# INTELMOTICS.net
KiCad netlist of a schematic drawn in EAGLE
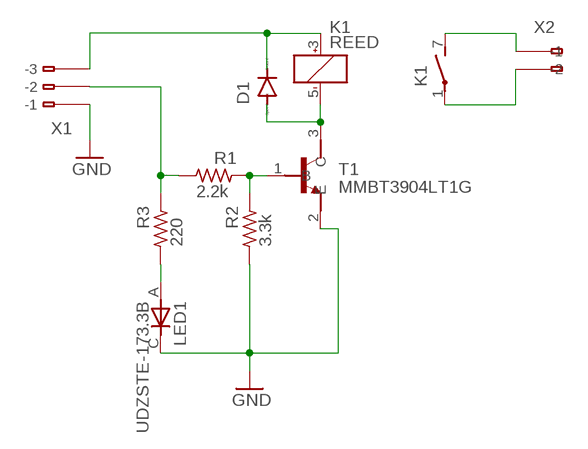
[diagram p0: schematic, sheet 1]

(export (version "E")
  (design (tool "Eeschema 10.0.6"))
  (components
    (comp (ref "D1")
      (value "MBR0520LT")
      (footprint "eagle-import:SOD123")
      (libsource (lib "eagle-import") (part "MBR0520LT"))
    )
    (comp (ref "K1")
      (value "REED")
      (footprint "eagle-import:REED")
      (libsource (lib "eagle-import") (part "REED"))
    )
    (comp (ref "LED1")
      (value "UDZSTE-173.3B")
      (footprint "eagle-import:SODFL2512X90N")
      (fields (field (name "MF") "Rohm"))
      (libsource (lib "eagle-import") (part "UDZSTE-173.3B"))
    )
    (comp (ref "R1")
      (value "2.2k")
      (footprint "eagle-import:R1206W")
      (libsource (lib "eagle-import") (part "R_1206W"))
    )
    (comp (ref "R2")
      (value "3.3k")
      (footprint "eagle-import:R1206W")
      (libsource (lib "eagle-import") (part "R_1206W"))
    )
    (comp (ref "R3")
      (value "220")
      (footprint "eagle-import:R1206W")
      (libsource (lib "eagle-import") (part "R_1206W"))
    )
    (comp (ref "T1")
      (value "MMBT3904LT1G")
      (footprint "eagle-import:SOT95P240X111-3N")
      (fields (field (name "MF") "ON Semiconductor"))
      (libsource (lib "eagle-import") (part "MMBT3904LT1G"))
    )
    (comp (ref "X1")
      (value "234-203")
      (footprint "eagle-import:234-203")
      (libsource (lib "eagle-import") (part "234-203"))
    )
    (comp (ref "X2")
      (value "234-502")
      (footprint "eagle-import:234-502")
      (libsource (lib "eagle-import") (part "234-502"))
    )
  )
  (nets
    (net (code "1") (name "GND") (class "Default")
      (node (ref "LED1") (pin "C") (pinfunction "C_C") (pintype "passive"))
      (node (ref "R2") (pin "1") (pinfunction "1_1") (pintype "passive"))
      (node (ref "T1") (pin "2") (pinfunction "E_2") (pintype "passive"))
      (node (ref "X1") (pin "B1") (pinfunction "B-1_B1") (pintype "passive"))
    )
    (net (code "2") (name "Net-(K1A-+)") (class "Default")
      (node (ref "D1") (pin "C") (pinfunction "C_C") (pintype "passive"))
      (node (ref "K1") (pin "3") (pinfunction "+_3") (pintype "passive"))
      (node (ref "X1") (pin "B3") (pinfunction "B-3_B3") (pintype "passive"))
    )
    (net (code "3") (name "Net-(K1A--)") (class "Default")
      (node (ref "D1") (pin "A") (pinfunction "A_A") (pintype "passive"))
      (node (ref "K1") (pin "5") (pinfunction "-_5") (pintype "passive"))
      (node (ref "T1") (pin "3") (pinfunction "C_3") (pintype "passive"))
    )
    (net (code "4") (name "Net-(K1B-P)") (class "Default")
      (node (ref "K1") (pin "1") (pinfunction "P_1") (pintype "passive"))
      (node (ref "X2") (pin "A2") (pinfunction "-2_A2") (pintype "passive"))
    )
    (net (code "5") (name "Net-(K1B-S)") (class "Default")
      (node (ref "K1") (pin "7") (pinfunction "S_7") (pintype "passive"))
      (node (ref "X2") (pin "A1") (pinfunction "-1_A1") (pintype "passive"))
    )
    (net (code "6") (name "Net-(LED1-PadA)") (class "Default")
      (node (ref "LED1") (pin "A") (pinfunction "A_A") (pintype "passive"))
      (node (ref "R3") (pin "1") (pinfunction "1_1") (pintype "passive"))
    )
    (net (code "7") (name "Net-(T1-B)") (class "Default")
      (node (ref "R1") (pin "2") (pinfunction "2_2") (pintype "passive"))
      (node (ref "R2") (pin "2") (pinfunction "2_2") (pintype "passive"))
      (node (ref "T1") (pin "1") (pinfunction "B_1") (pintype "passive"))
    )
    (net (code "8") (name "Net-(X1-B-2)") (class "Default")
      (node (ref "R1") (pin "1") (pinfunction "1_1") (pintype "passive"))
      (node (ref "R3") (pin "2") (pinfunction "2_2") (pintype "passive"))
      (node (ref "X1") (pin "B2") (pinfunction "B-2_B2") (pintype "passive"))
    )
    (net (code "9") (name "unconnected-(X1--1-PadA1)") (class "Default")
      (node (ref "X1") (pin "A1") (pinfunction "-1_A1") (pintype "passive"))
    )
    (net (code "10") (name "unconnected-(X1--2-PadA2)") (class "Default")
      (node (ref "X1") (pin "A2") (pinfunction "-2_A2") (pintype "passive"))
    )
    (net (code "11") (name "unconnected-(X1--3-PadA3)") (class "Default")
      (node (ref "X1") (pin "A3") (pinfunction "-3_A3") (pintype "passive"))
    )
    (net (code "12") (name "unconnected-(X2-B-1-PadB1)") (class "Default")
      (node (ref "X2") (pin "B1") (pinfunction "B-1_B1") (pintype "passive"))
    )
    (net (code "13") (name "unconnected-(X2-B-2-PadB2)") (class "Default")
      (node (ref "X2") (pin "B2") (pinfunction "B-2_B2") (pintype "passive"))
    )
  )
)
